# SMARTBALL_v2_2.net
KiCad netlist of a schematic drawn in EAGLE
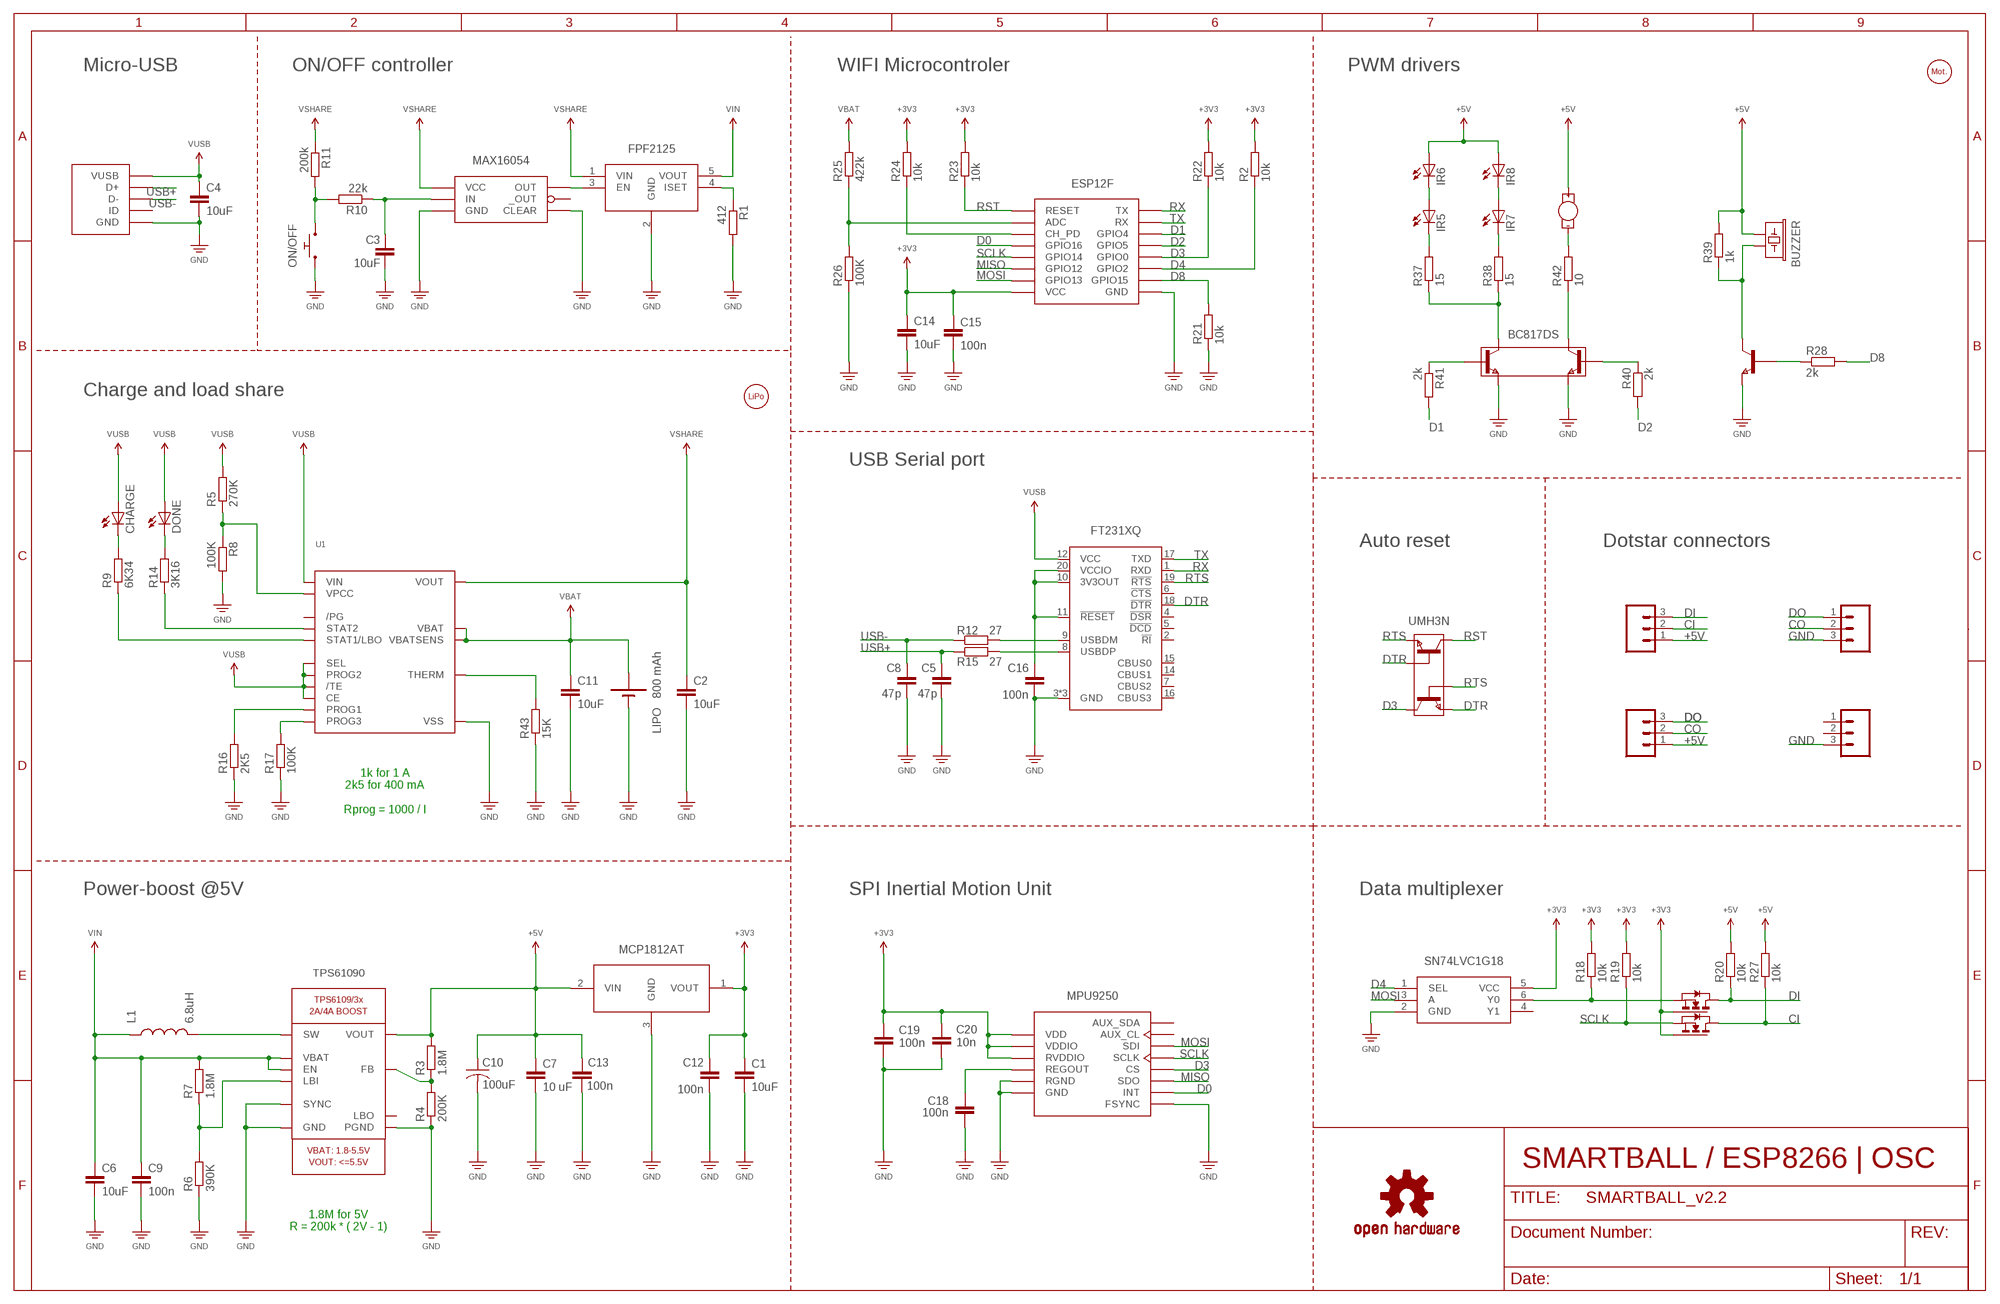
[diagram p0: schematic, sheet 1]

(export (version "E")
  (design (tool "Eeschema 10.0.6"))
  (components
    (comp (ref "BC817DS")
      (value "SOT_BC817DS")
      (footprint "eagle-import:SOT457R_PHILIPS")
      (libsource (lib "eagle-import") (part "SOT_BC817DS"))
    )
    (comp (ref "BUZZER")
      (value "BUZZER_PKMCS0909E4000-R1")
      (footprint "eagle-import:BUZZER_PKMCS0909E4000-R1")
      (libsource (lib "eagle-import") (part "BUZZER_PKMCS0909E4000-R1"))
    )
    (comp (ref "C1")
      (value "10uF")
      (footprint "eagle-import:C0603")
      (libsource (lib "eagle-import") (part "CAP_CERAMICC0603K"))
    )
    (comp (ref "C2")
      (value "10uF")
      (footprint "eagle-import:C0603")
      (libsource (lib "eagle-import") (part "CAP_CERAMICC0603K"))
    )
    (comp (ref "C3")
      (value "10uF")
      (footprint "eagle-import:C0603")
      (libsource (lib "eagle-import") (part "CAP_CERAMICC0603K"))
    )
    (comp (ref "C4")
      (value "10uF")
      (footprint "eagle-import:C0603")
      (libsource (lib "eagle-import") (part "CAP_CERAMICC0603K"))
    )
    (comp (ref "C5")
      (value "47p")
      (footprint "eagle-import:C0603")
      (libsource (lib "eagle-import") (part "CAP_CERAMICC0603K"))
    )
    (comp (ref "C6")
      (value "10uF")
      (footprint "eagle-import:C0603")
      (libsource (lib "eagle-import") (part "CAP_CERAMICC0603K"))
    )
    (comp (ref "C7")
      (value "10 uF")
      (footprint "eagle-import:C0603")
      (libsource (lib "eagle-import") (part "CAP_CERAMICC0603K"))
    )
    (comp (ref "C8")
      (value "47p")
      (footprint "eagle-import:C0603")
      (libsource (lib "eagle-import") (part "CAP_CERAMICC0603K"))
    )
    (comp (ref "C9")
      (value "100n")
      (footprint "eagle-import:C0603")
      (libsource (lib "eagle-import") (part "CAP_CERAMICC0603K"))
    )
    (comp (ref "C10")
      (value "100uF")
      (footprint "eagle-import:C1210")
      (libsource (lib "eagle-import") (part "CAP_TANTALUMC1210"))
    )
    (comp (ref "C11")
      (value "10uF")
      (footprint "eagle-import:C0603")
      (libsource (lib "eagle-import") (part "CAP_CERAMICC0603K"))
    )
    (comp (ref "C12")
      (value "100n")
      (footprint "eagle-import:C0603")
      (libsource (lib "eagle-import") (part "CAP_CERAMICC0603K"))
    )
    (comp (ref "C13")
      (value "100n")
      (footprint "eagle-import:C0603")
      (libsource (lib "eagle-import") (part "CAP_CERAMICC0603K"))
    )
    (comp (ref "C14")
      (value "10uF")
      (footprint "eagle-import:C0603")
      (libsource (lib "eagle-import") (part "CAP_CERAMICC0603K"))
    )
    (comp (ref "C15")
      (value "100n")
      (footprint "eagle-import:C0603")
      (libsource (lib "eagle-import") (part "CAP_CERAMICC0603K"))
    )
    (comp (ref "C16")
      (value "100n")
      (footprint "eagle-import:C0603")
      (libsource (lib "eagle-import") (part "CAP_CERAMICC0603K"))
    )
    (comp (ref "C18")
      (value "100n")
      (footprint "eagle-import:C0603")
      (libsource (lib "eagle-import") (part "CAP_CERAMICC0603K"))
    )
    (comp (ref "C19")
      (value "100n")
      (footprint "eagle-import:C0603")
      (libsource (lib "eagle-import") (part "CAP_CERAMICC0603K"))
    )
    (comp (ref "C20")
      (value "10n")
      (footprint "eagle-import:C0603")
      (libsource (lib "eagle-import") (part "CAP_CERAMICC0603K"))
    )
    (comp (ref "CHARGE")
      (value "LED_KINGBRIGHT_16X08")
      (footprint "eagle-import:LED_KINGBRIGHT_16X08")
      (libsource (lib "eagle-import") (part "LED_KINGBRIGHT_16X08"))
    )
    (comp (ref "DONE")
      (value "LED_KINGBRIGHT_16X08")
      (footprint "eagle-import:LED_KINGBRIGHT_16X08")
      (libsource (lib "eagle-import") (part "LED_KINGBRIGHT_16X08"))
    )
    (comp (ref "ESP12F")
      (value "µP_ESP12")
      (footprint "eagle-import:µP_ESP12")
      (libsource (lib "eagle-import") (part "µP_ESP12"))
    )
    (comp (ref "FT231XQ")
      (value "QFN_FT231X")
      (footprint "eagle-import:QFN20")
      (libsource (lib "eagle-import") (part "QFN_FT231X"))
    )
    (comp (ref "IR5")
      (value "LED_SFH4050")
      (footprint "eagle-import:LED_SFH4050")
      (libsource (lib "eagle-import") (part "LED_SFH4050"))
    )
    (comp (ref "IR6")
      (value "LED_SFH4050")
      (footprint "eagle-import:LED_SFH4050")
      (libsource (lib "eagle-import") (part "LED_SFH4050"))
    )
    (comp (ref "IR7")
      (value "LED_SFH4050")
      (footprint "eagle-import:LED_SFH4050")
      (libsource (lib "eagle-import") (part "LED_SFH4050"))
    )
    (comp (ref "IR8")
      (value "LED_SFH4050")
      (footprint "eagle-import:LED_SFH4050")
      (libsource (lib "eagle-import") (part "LED_SFH4050"))
    )
    (comp (ref "J1")
      (value "CONN_USB")
      (footprint "eagle-import:CONN_USB")
      (libsource (lib "eagle-import") (part "CONN_USB"))
    )
    (comp (ref "L1")
      (value "6.8uH")
      (footprint "eagle-import:IND_ASPIAIG-S4035")
      (libsource (lib "eagle-import") (part "IND_ASPIAIG-S4035"))
    )
    (comp (ref "LIPO")
      (value "CONN_BATTERY")
      (footprint "eagle-import:CONN_WIRES")
      (libsource (lib "eagle-import") (part "CONN_BATTERY"))
    )
    (comp (ref "LOGO1")
      (value "LOGO_OSHWL")
      (footprint "eagle-import:LOGO_OSHW")
      (libsource (lib "eagle-import") (part "LOGO_OSHWL"))
    )
    (comp (ref "MOTOR")
      (value "CONN_MOTOR")
      (footprint "eagle-import:CONN_WIRES")
      (libsource (lib "eagle-import") (part "CONN_MOTOR"))
    )
    (comp (ref "ON/OFF")
      (value "BUT_KMR6")
      (footprint "eagle-import:BUT_KMR6")
      (libsource (lib "eagle-import") (part "BUT_KMR6"))
    )
    (comp (ref "R1")
      (value "412")
      (footprint "eagle-import:R0402")
      (libsource (lib "eagle-import") (part "RES_EUR0402"))
    )
    (comp (ref "R2")
      (value "10k")
      (footprint "eagle-import:R0402")
      (libsource (lib "eagle-import") (part "RES_EUR0402"))
    )
    (comp (ref "R3")
      (value "1.8M")
      (footprint "eagle-import:R0402")
      (libsource (lib "eagle-import") (part "RES_EUR0402"))
    )
    (comp (ref "R4")
      (value "200K")
      (footprint "eagle-import:R0402")
      (libsource (lib "eagle-import") (part "RES_EUR0402"))
    )
    (comp (ref "R5")
      (value "270K")
      (footprint "eagle-import:R0402")
      (libsource (lib "eagle-import") (part "RES_EUR0402"))
    )
    (comp (ref "R6")
      (value "390K")
      (footprint "eagle-import:R0402")
      (libsource (lib "eagle-import") (part "RES_EUR0402"))
    )
    (comp (ref "R7")
      (value "1.8M")
      (footprint "eagle-import:R0402")
      (libsource (lib "eagle-import") (part "RES_EUR0402"))
    )
    (comp (ref "R8")
      (value "100K")
      (footprint "eagle-import:R0402")
      (libsource (lib "eagle-import") (part "RES_EUR0402"))
    )
    (comp (ref "R9")
      (value "6K34")
      (footprint "eagle-import:R0402")
      (libsource (lib "eagle-import") (part "RES_EUR0402"))
    )
    (comp (ref "R10")
      (value "22k")
      (footprint "eagle-import:R0402")
      (libsource (lib "eagle-import") (part "RES_EUR0402"))
    )
    (comp (ref "R11")
      (value "200k")
      (footprint "eagle-import:R0402")
      (libsource (lib "eagle-import") (part "RES_EUR0402"))
    )
    (comp (ref "R12")
      (value "27")
      (footprint "eagle-import:R0402")
      (libsource (lib "eagle-import") (part "RES_EUR0402"))
    )
    (comp (ref "R14")
      (value "3K16")
      (footprint "eagle-import:R0402")
      (libsource (lib "eagle-import") (part "RES_EUR0402"))
    )
    (comp (ref "R15")
      (value "27")
      (footprint "eagle-import:R0402")
      (libsource (lib "eagle-import") (part "RES_EUR0402"))
    )
    (comp (ref "R16")
      (value "2K5")
      (footprint "eagle-import:R0402")
      (libsource (lib "eagle-import") (part "RES_EUR0402"))
    )
    (comp (ref "R17")
      (value "100K")
      (footprint "eagle-import:R0402")
      (libsource (lib "eagle-import") (part "RES_EUR0402"))
    )
    (comp (ref "R18")
      (value "10k")
      (footprint "eagle-import:R0402")
      (libsource (lib "eagle-import") (part "RES_EUR0402"))
    )
    (comp (ref "R19")
      (value "10k")
      (footprint "eagle-import:R0402")
      (libsource (lib "eagle-import") (part "RES_EUR0402"))
    )
    (comp (ref "R20")
      (value "10k")
      (footprint "eagle-import:R0402")
      (libsource (lib "eagle-import") (part "RES_EUR0402"))
    )
    (comp (ref "R21")
      (value "10k")
      (footprint "eagle-import:R0402")
      (libsource (lib "eagle-import") (part "RES_EUR0402"))
    )
    (comp (ref "R22")
      (value "10k")
      (footprint "eagle-import:R0402")
      (libsource (lib "eagle-import") (part "RES_EUR0402"))
    )
    (comp (ref "R23")
      (value "10k")
      (footprint "eagle-import:R0402")
      (libsource (lib "eagle-import") (part "RES_EUR0402"))
    )
    (comp (ref "R24")
      (value "10k")
      (footprint "eagle-import:R0402")
      (libsource (lib "eagle-import") (part "RES_EUR0402"))
    )
    (comp (ref "R25")
      (value "422k")
      (footprint "eagle-import:R0402")
      (libsource (lib "eagle-import") (part "RES_EUR0402"))
    )
    (comp (ref "R26")
      (value "100K")
      (footprint "eagle-import:R0402")
      (libsource (lib "eagle-import") (part "RES_EUR0402"))
    )
    (comp (ref "R27")
      (value "10k")
      (footprint "eagle-import:R0402")
      (libsource (lib "eagle-import") (part "RES_EUR0402"))
    )
    (comp (ref "R28")
      (value "2k")
      (footprint "eagle-import:R0402")
      (libsource (lib "eagle-import") (part "RES_EUR0402"))
    )
    (comp (ref "R37")
      (value "15")
      (footprint "eagle-import:R0402")
      (libsource (lib "eagle-import") (part "RES_EUR0402"))
    )
    (comp (ref "R38")
      (value "15")
      (footprint "eagle-import:R0402")
      (libsource (lib "eagle-import") (part "RES_EUR0402"))
    )
    (comp (ref "R39")
      (value "1k")
      (footprint "eagle-import:R0402")
      (libsource (lib "eagle-import") (part "RES_EUR0402"))
    )
    (comp (ref "R40")
      (value "2k")
      (footprint "eagle-import:R0402")
      (libsource (lib "eagle-import") (part "RES_EUR0402"))
    )
    (comp (ref "R41")
      (value "2k")
      (footprint "eagle-import:R0402")
      (libsource (lib "eagle-import") (part "RES_EUR0402"))
    )
    (comp (ref "R42")
      (value "10")
      (footprint "eagle-import:R0402")
      (libsource (lib "eagle-import") (part "RES_EUR0402"))
    )
    (comp (ref "R43")
      (value "15K")
      (footprint "eagle-import:R0402")
      (libsource (lib "eagle-import") (part "RES_EUR0402"))
    )
    (comp (ref "TPS61090")
      (value "TPS61090RSAR")
      (footprint "eagle-import:QFN16")
      (libsource (lib "eagle-import") (part "QFN_TPS6103X"))
    )
    (comp (ref "U$2")
      (value "SOT_FPF2125")
      (footprint "eagle-import:SOT23-5")
      (libsource (lib "eagle-import") (part "SOT_FPF2125"))
    )
    (comp (ref "U$3")
      (value "SOT_MCP11812AT")
      (footprint "eagle-import:SOT23-3")
      (libsource (lib "eagle-import") (part "SOT_MCP11812AT"))
    )
    (comp (ref "U$5")
      (value "CONN_03_SMD")
      (footprint "eagle-import:CONN_03_SMD")
      (libsource (lib "eagle-import") (part "CONN_03_SMD"))
    )
    (comp (ref "U$6")
      (value "CONN_03_SMD")
      (footprint "eagle-import:CONN_03_SMD")
      (libsource (lib "eagle-import") (part "CONN_03_SMD"))
    )
    (comp (ref "U$12")
      (value "SOT_MAX16054")
      (footprint "eagle-import:TSOT23-6")
      (libsource (lib "eagle-import") (part "SOT_MAX16054"))
    )
    (comp (ref "U$14")
      (value "CONN_03_SMD")
      (footprint "eagle-import:CONN_03_SMD")
      (libsource (lib "eagle-import") (part "CONN_03_SMD"))
    )
    (comp (ref "U$15")
      (value "CONN_03_SMD")
      (footprint "eagle-import:CONN_03_SMD")
      (libsource (lib "eagle-import") (part "CONN_03_SMD"))
    )
    (comp (ref "U$19")
      (value "MOTOR_BODY")
      (footprint "eagle-import:MOTOR_BODY")
      (libsource (lib "eagle-import") (part "MOTOR_BODY"))
    )
    (comp (ref "U$20")
      (value "SOT_SN74LVC1G18")
      (footprint "eagle-import:SOT363")
      (libsource (lib "eagle-import") (part "SOT_SN74LVC1G18"))
    )
    (comp (ref "U$21")
      (value "QFN_MPU-9250QFN24G")
      (footprint "eagle-import:QFN24_3MM")
      (libsource (lib "eagle-import") (part "QFN_MPU-9250QFN24G"))
    )
    (comp (ref "U$22")
      (value "SOT_2N7002PS")
      (footprint "eagle-import:SOT363")
      (libsource (lib "eagle-import") (part "SOT_2N7002PS"))
    )
    (comp (ref "U$28")
      (value "SOT_SBC847AWT1G")
      (footprint "eagle-import:SOT323")
      (libsource (lib "eagle-import") (part "SOT_SBC847AWT1G"))
    )
    (comp (ref "U$29")
      (value "BATT_BODY")
      (footprint "eagle-import:BATT_BODY")
      (libsource (lib "eagle-import") (part "BATT_BODY"))
    )
    (comp (ref "U1")
      (value "QFN_MCP73871")
      (footprint "eagle-import:QFN20")
      (libsource (lib "eagle-import") (part "QFN_MCP73871"))
    )
    (comp (ref "UMH3N")
      (value "SOT_UMH3N")
      (footprint "eagle-import:SOT363")
      (libsource (lib "eagle-import") (part "SOT_UMH3N"))
    )
  )
  (nets
    (net (code "1") (name "+3V3") (class "Default")
      (node (ref "C1") (pin "1") (pinfunction "1_1") (pintype "passive"))
      (node (ref "C12") (pin "1") (pinfunction "1_1") (pintype "passive"))
      (node (ref "C14") (pin "1") (pinfunction "1_1") (pintype "passive"))
      (node (ref "C15") (pin "1") (pinfunction "1_1") (pintype "passive"))
      (node (ref "C19") (pin "1") (pinfunction "1_1") (pintype "passive"))
      (node (ref "C20") (pin "2") (pinfunction "2_2") (pintype "passive"))
      (node (ref "ESP12F") (pin "VCC") (pinfunction "VCC_VCC") (pintype "bidirectional"))
      (node (ref "R18") (pin "2") (pinfunction "2_2") (pintype "passive"))
      (node (ref "R19") (pin "2") (pinfunction "2_2") (pintype "passive"))
      (node (ref "R2") (pin "2") (pinfunction "2_2") (pintype "passive"))
      (node (ref "R22") (pin "2") (pinfunction "2_2") (pintype "passive"))
      (node (ref "R23") (pin "2") (pinfunction "2_2") (pintype "passive"))
      (node (ref "R24") (pin "2") (pinfunction "2_2") (pintype "passive"))
      (node (ref "U$20") (pin "5") (pinfunction "VCC_5") (pintype "bidirectional"))
      (node (ref "U$21") (pin "1") (pinfunction "RVDDIO_1") (pintype "bidirectional"))
      (node (ref "U$21") (pin "13") (pinfunction "VDD_13") (pintype "bidirectional"))
      (node (ref "U$21") (pin "8") (pinfunction "VDDIO_8") (pintype "bidirectional"))
      (node (ref "U$22") (pin "2") (pinfunction "G1_2") (pintype "passive"))
      (node (ref "U$22") (pin "5") (pinfunction "G2_5") (pintype "passive"))
      (node (ref "U$3") (pin "1") (pinfunction "VOUT_1") (pintype "bidirectional"))
    )
    (net (code "2") (name "+5V") (class "Default")
      (node (ref "BUZZER") (pin "1") (pinfunction "1_1") (pintype "passive"))
      (node (ref "C10") (pin "1") (pinfunction "1_1") (pintype "passive"))
      (node (ref "C13") (pin "1") (pinfunction "1_1") (pintype "passive"))
      (node (ref "C7") (pin "1") (pinfunction "1_1") (pintype "passive"))
      (node (ref "IR6") (pin "1") (pinfunction "A_1") (pintype "passive"))
      (node (ref "IR8") (pin "1") (pinfunction "A_1") (pintype "passive"))
      (node (ref "MOTOR") (pin "VCC") (pinfunction "+_VCC") (pintype "bidirectional"))
      (node (ref "R20") (pin "2") (pinfunction "2_2") (pintype "passive"))
      (node (ref "R27") (pin "2") (pinfunction "2_2") (pintype "passive"))
      (node (ref "R3") (pin "2") (pinfunction "2_2") (pintype "passive"))
      (node (ref "R39") (pin "2") (pinfunction "2_2") (pintype "passive"))
      (node (ref "TPS61090") (pin "1") (pinfunction "VOUT_1") (pintype "power_in"))
      (node (ref "TPS61090") (pin "15") (pinfunction "VOUT_15") (pintype "power_in"))
      (node (ref "TPS61090") (pin "16") (pinfunction "VOUT_16") (pintype "power_in"))
      (node (ref "U$15") (pin "1") (pinfunction "1_1") (pintype "passive"))
      (node (ref "U$3") (pin "2") (pinfunction "VIN_2") (pintype "bidirectional"))
      (node (ref "U$5") (pin "1") (pinfunction "1_1") (pintype "passive"))
    )
    (net (code "3") (name "/CI") (class "Default")
      (node (ref "R27") (pin "1") (pinfunction "1_1") (pintype "passive"))
      (node (ref "U$22") (pin "3") (pinfunction "D2_3") (pintype "passive"))
      (node (ref "U$5") (pin "2") (pinfunction "2_2") (pintype "passive"))
    )
    (net (code "4") (name "/CO") (class "Default")
      (node (ref "U$15") (pin "2") (pinfunction "2_2") (pintype "passive"))
      (node (ref "U$6") (pin "2") (pinfunction "2_2") (pintype "passive"))
    )
    (net (code "5") (name "/D0") (class "Default")
      (node (ref "ESP12F") (pin "GPIO16") (pinfunction "GPIO16_GPIO16") (pintype "bidirectional"))
      (node (ref "U$21") (pin "12") (pinfunction "INT_12") (pintype "bidirectional"))
    )
    (net (code "6") (name "/D1") (class "Default")
      (node (ref "ESP12F") (pin "GPIO4") (pinfunction "GPIO4_GPIO4") (pintype "bidirectional"))
      (node (ref "R41") (pin "2") (pinfunction "2_2") (pintype "passive"))
    )
    (net (code "7") (name "/D2") (class "Default")
      (node (ref "ESP12F") (pin "GPIO5") (pinfunction "GPIO5_GPIO5") (pintype "bidirectional"))
      (node (ref "R40") (pin "2") (pinfunction "2_2") (pintype "passive"))
    )
    (net (code "8") (name "/D3") (class "Default")
      (node (ref "ESP12F") (pin "GPIO0") (pinfunction "GPIO0_GPIO0") (pintype "bidirectional"))
      (node (ref "R22") (pin "1") (pinfunction "1_1") (pintype "passive"))
      (node (ref "U$21") (pin "22") (pinfunction "CS_22") (pintype "bidirectional"))
      (node (ref "UMH3N") (pin "3") (pinfunction "C2_3") (pintype "passive"))
    )
    (net (code "9") (name "/D4") (class "Default")
      (node (ref "ESP12F") (pin "GPIO2") (pinfunction "GPIO2_GPIO2") (pintype "bidirectional"))
      (node (ref "R2") (pin "1") (pinfunction "1_1") (pintype "passive"))
      (node (ref "U$20") (pin "1") (pinfunction "SEL_1") (pintype "bidirectional"))
    )
    (net (code "10") (name "/D8") (class "Default")
      (node (ref "ESP12F") (pin "GPIO15") (pinfunction "GPIO15_GPIO15") (pintype "bidirectional"))
      (node (ref "R21") (pin "2") (pinfunction "2_2") (pintype "passive"))
      (node (ref "R28") (pin "2") (pinfunction "2_2") (pintype "passive"))
    )
    (net (code "11") (name "/DI") (class "Default")
      (node (ref "R20") (pin "1") (pinfunction "1_1") (pintype "passive"))
      (node (ref "U$22") (pin "6") (pinfunction "D1_6") (pintype "passive"))
      (node (ref "U$5") (pin "3") (pinfunction "3_3") (pintype "passive"))
    )
    (net (code "12") (name "/DO") (class "Default")
      (node (ref "U$15") (pin "3") (pinfunction "3_3") (pintype "passive"))
      (node (ref "U$6") (pin "1") (pinfunction "1_1") (pintype "passive"))
    )
    (net (code "13") (name "/DTR") (class "Default")
      (node (ref "FT231XQ") (pin "18") (pinfunction "~{DTR}_18") (pintype "bidirectional"))
      (node (ref "UMH3N") (pin "2") (pinfunction "B1_2") (pintype "passive"))
      (node (ref "UMH3N") (pin "4") (pinfunction "E2_4") (pintype "passive"))
    )
    (net (code "14") (name "/MISO") (class "Default")
      (node (ref "ESP12F") (pin "GPIO12") (pinfunction "GPIO12_GPIO12") (pintype "bidirectional"))
      (node (ref "U$21") (pin "9") (pinfunction "SDO_9") (pintype "bidirectional"))
    )
    (net (code "15") (name "/MOSI") (class "Default")
      (node (ref "ESP12F") (pin "GPIO13") (pinfunction "GPIO13_GPIO13") (pintype "bidirectional"))
      (node (ref "U$20") (pin "3") (pinfunction "A_3") (pintype "bidirectional"))
      (node (ref "U$21") (pin "24") (pinfunction "SDI_24") (pintype "bidirectional"))
    )
    (net (code "16") (name "/RST") (class "Default")
      (node (ref "ESP12F") (pin "RESET") (pinfunction "RESET_RESET") (pintype "bidirectional"))
      (node (ref "R23") (pin "1") (pinfunction "1_1") (pintype "passive"))
      (node (ref "UMH3N") (pin "6") (pinfunction "C1_6") (pintype "passive"))
    )
    (net (code "17") (name "/RTS") (class "Default")
      (node (ref "FT231XQ") (pin "19") (pinfunction "~{RTS}_19") (pintype "bidirectional"))
      (node (ref "UMH3N") (pin "1") (pinfunction "E1_1") (pintype "passive"))
      (node (ref "UMH3N") (pin "5") (pinfunction "B2_5") (pintype "passive"))
    )
    (net (code "18") (name "/RX") (class "Default")
      (node (ref "ESP12F") (pin "TX") (pinfunction "TX_TX") (pintype "bidirectional"))
      (node (ref "FT231XQ") (pin "1") (pinfunction "RXD_1") (pintype "bidirectional"))
    )
    (net (code "19") (name "/SCLK") (class "Default")
      (node (ref "ESP12F") (pin "GPIO14") (pinfunction "GPIO14_GPIO14") (pintype "bidirectional"))
      (node (ref "R19") (pin "1") (pinfunction "1_1") (pintype "passive"))
      (node (ref "U$21") (pin "23") (pinfunction "SCLK_23") (pintype "bidirectional"))
      (node (ref "U$22") (pin "4") (pinfunction "S2_4") (pintype "passive"))
    )
    (net (code "20") (name "/TX") (class "Default")
      (node (ref "ESP12F") (pin "RX") (pinfunction "RX_RX") (pintype "bidirectional"))
      (node (ref "FT231XQ") (pin "17") (pinfunction "TXD_17") (pintype "bidirectional"))
    )
    (net (code "21") (name "/USB+") (class "Default")
      (node (ref "C5") (pin "1") (pinfunction "1_1") (pintype "passive"))
      (node (ref "J1") (pin "D+") (pinfunction "D+_D+") (pintype "bidirectional"))
      (node (ref "R15") (pin "1") (pinfunction "1_1") (pintype "passive"))
    )
    (net (code "22") (name "/USB-") (class "Default")
      (node (ref "C8") (pin "1") (pinfunction "1_1") (pintype "passive"))
      (node (ref "J1") (pin "D-") (pinfunction "D-_D-") (pintype "bidirectional"))
      (node (ref "R12") (pin "1") (pinfunction "1_1") (pintype "passive"))
    )
    (net (code "23") (name "GND") (class "Default")
      (node (ref "BC817DS") (pin "1") (pinfunction "E1_1") (pintype "passive"))
      (node (ref "BC817DS") (pin "4") (pinfunction "E2_4") (pintype "passive"))
      (node (ref "C1") (pin "2") (pinfunction "2_2") (pintype "passive"))
      (node (ref "C10") (pin "2") (pinfunction "2_2") (pintype "passive"))
      (node (ref "C11") (pin "2") (pinfunction "2_2") (pintype "passive"))
      (node (ref "C12") (pin "2") (pinfunction "2_2") (pintype "passive"))
      (node (ref "C13") (pin "2") (pinfunction "2_2") (pintype "passive"))
      (node (ref "C14") (pin "2") (pinfunction "2_2") (pintype "passive"))
      (node (ref "C15") (pin "2") (pinfunction "2_2") (pintype "passive"))
      (node (ref "C16") (pin "2") (pinfunction "2_2") (pintype "passive"))
      (node (ref "C18") (pin "2") (pinfunction "2_2") (pintype "passive"))
      (node (ref "C19") (pin "2") (pinfunction "2_2") (pintype "passive"))
      (node (ref "C2") (pin "2") (pinfunction "2_2") (pintype "passive"))
      (node (ref "C20") (pin "1") (pinfunction "1_1") (pintype "passive"))
      (node (ref "C3") (pin "2") (pinfunction "2_2") (pintype "passive"))
      (node (ref "C4") (pin "2") (pinfunction "2_2") (pintype "passive"))
      (node (ref "C5") (pin "2") (pinfunction "2_2") (pintype "passive"))
      (node (ref "C6") (pin "2") (pinfunction "2_2") (pintype "passive"))
      (node (ref "C7") (pin "2") (pinfunction "2_2") (pintype "passive"))
      (node (ref "C8") (pin "2") (pinfunction "2_2") (pintype "passive"))
      (node (ref "C9") (pin "2") (pinfunction "2_2") (pintype "passive"))
      (node (ref "ESP12F") (pin "GND") (pinfunction "GND_GND") (pintype "bidirectional"))
      (node (ref "FT231XQ") (pin "13") (pinfunction "GND_13") (pintype "bidirectional"))
      (node (ref "FT231XQ") (pin "3") (pinfunction "GND_3") (pintype "bidirectional"))
      (node (ref "FT231XQ") (pin "EXP") (pinfunction "GND_EXP") (pintype "bidirectional"))
      (node (ref "J1") (pin "GND") (pinfunction "GND_GND") (pintype "bidirectional"))
      (node (ref "J1") (pin "P$1") (pinfunction "GND_P$1") (pintype "bidirectional"))
      (node (ref "J1") (pin "P$11") (pinfunction "GND_P$11") (pintype "bidirectional"))
      (node (ref "J1") (pin "SHELL1") (pinfunction "GND_SHELL1") (pintype "bidirectional"))
      (node (ref "J1") (pin "SHELL2") (pinfunction "GND_SHELL2") (pintype "bidirectional"))
      (node (ref "J1") (pin "SHELL5") (pinfunction "GND_SHELL5") (pintype "bidirectional"))
      (node (ref "J1") (pin "SHELL6") (pinfunction "GND_SHELL6") (pintype "bidirectional"))
      (node (ref "LIPO") (pin "GND") (pinfunction "GND_GND") (pintype "power_in"))
      (node (ref "ON/OFF") (pin "1") (pinfunction "1_1") (pintype "passive"))
      (node (ref "ON/OFF") (pin "4") (pinfunction "1_4") (pintype "passive"))
      (node (ref "R1") (pin "2") (pinfunction "2_2") (pintype "passive"))
      (node (ref "R16") (pin "1") (pinfunction "1_1") (pintype "passive"))
      (node (ref "R17") (pin "1") (pinfunction "1_1") (pintype "passive"))
      (node (ref "R21") (pin "1") (pinfunction "1_1") (pintype "passive"))
      (node (ref "R26") (pin "1") (pinfunction "1_1") (pintype "passive"))
      (node (ref "R4") (pin "1") (pinfunction "1_1") (pintype "passive"))
      (node (ref "R43") (pin "1") (pinfunction "1_1") (pintype "passive"))
      (node (ref "R6") (pin "1") (pinfunction "1_1") (pintype "passive"))
      (node (ref "R8") (pin "2") (pinfunction "2_2") (pintype "passive"))
      (node (ref "TPS61090") (pin "10") (pinfunction "SYNC_10") (pintype "input"))
      (node (ref "TPS61090") (pin "13") (pinfunction "GND_13") (pintype "power_in"))
      (node (ref "TPS61090") (pin "5") (pinfunction "PGND_5") (pintype "power_in"))
      (node (ref "TPS61090") (pin "6") (pinfunction "PGND_6") (pintype "power_in"))
      (node (ref "TPS61090") (pin "7") (pinfunction "PGND_7") (pintype "power_in"))
      (node (ref "TPS61090") (pin "PAD") (pinfunction "PGND_PAD") (pintype "power_in"))
      (node (ref "U$12") (pin "2") (pinfunction "GND_2") (pintype "bidirectional"))
      (node (ref "U$12") (pin "3") (pinfunction "CLEAR_3") (pintype "bidirectional"))
      (node (ref "U$14") (pin "3") (pinfunction "3_3") (pintype "passive"))
      (node (ref "U$2") (pin "2") (pinfunction "GND_2") (pintype "bidirectional"))
      (node (ref "U$20") (pin "2") (pinfunction "GND_2") (pintype "bidirectional"))
      (node (ref "U$21") (pin "11") (pinfunction "FSYNC_11") (pintype "bidirectional"))
      (node (ref "U$21") (pin "18") (pinfunction "GND_18") (pintype "bidirectional"))
      (node (ref "U$21") (pin "20") (pinfunction "RGND_20") (pintype "bidirectional"))
      (node (ref "U$28") (pin "2") (pinfunction "E_2") (pintype "passive"))
      (node (ref "U$3") (pin "3") (pinfunction "GND_3") (pintype "bidirectional"))
      (node (ref "U$6") (pin "3") (pinfunction "3_3") (pintype "passive"))
      (node (ref "U1") (pin "10") (pinfunction "VSS_10") (pintype "bidirectional"))
      (node (ref "U1") (pin "11") (pinfunction "VSS_11") (pintype "bidirectional"))
      (node (ref "U1") (pin "EXP") (pinfunction "VSS_EXP") (pintype "bidirectional"))
    )
    (net (code "24") (name "Net-(BC817DS-B1)") (class "Default")
      (node (ref "BC817DS") (pin "2") (pinfunction "B1_2") (pintype "passive"))
      (node (ref "R40") (pin "1") (pinfunction "1_1") (pintype "passive"))
    )
    (net (code "25") (name "Net-(BC817DS-B2)") (class "Default")
      (node (ref "BC817DS") (pin "5") (pinfunction "B2_5") (pintype "passive"))
      (node (ref "R41") (pin "1") (pinfunction "1_1") (pintype "passive"))
    )
    (net (code "26") (name "Net-(BC817DS-C1)") (class "Default")
      (node (ref "BC817DS") (pin "6") (pinfunction "C1_6") (pintype "passive"))
      (node (ref "R42") (pin "1") (pinfunction "1_1") (pintype "passive"))
    )
    (net (code "27") (name "Net-(BC817DS-C2)") (class "Default")
      (node (ref "BC817DS") (pin "3") (pinfunction "C2_3") (pintype "passive"))
      (node (ref "R37") (pin "1") (pinfunction "1_1") (pintype "passive"))
      (node (ref "R38") (pin "1") (pinfunction "1_1") (pintype "passive"))
    )
    (net (code "28") (name "Net-(CHARGE-C)") (class "Default")
      (node (ref "CHARGE") (pin "2") (pinfunction "C_2") (pintype "passive"))
      (node (ref "R9") (pin "2") (pinfunction "2_2") (pintype "passive"))
    )
    (net (code "29") (name "Net-(DONE-C)") (class "Default")
      (node (ref "DONE") (pin "2") (pinfunction "C_2") (pintype "passive"))
      (node (ref "R14") (pin "2") (pinfunction "2_2") (pintype "passive"))
    )
    (net (code "30") (name "Net-(ESP12F-PadADC)") (class "Default")
      (node (ref "ESP12F") (pin "ADC") (pinfunction "ADC_ADC") (pintype "bidirectional"))
      (node (ref "R25") (pin "1") (pinfunction "1_1") (pintype "passive"))
      (node (ref "R26") (pin "2") (pinfunction "2_2") (pintype "passive"))
    )
    (net (code "31") (name "Net-(ESP12F-PadCH_PD)") (class "Default")
      (node (ref "ESP12F") (pin "CH_PD") (pinfunction "CH_PD_CH_PD") (pintype "bidirectional"))
      (node (ref "R24") (pin "1") (pinfunction "1_1") (pintype "passive"))
    )
    (net (code "32") (name "Net-(FT231XQ-3V3OUT)") (class "Default")
      (node (ref "C16") (pin "1") (pinfunction "1_1") (pintype "passive"))
      (node (ref "FT231XQ") (pin "10") (pinfunction "3V3OUT_10") (pintype "bidirectional"))
      (node (ref "FT231XQ") (pin "11") (pinfunction "~{RESET}_11") (pintype "bidirectional"))
      (node (ref "FT231XQ") (pin "20") (pinfunction "VCCIO_20") (pintype "bidirectional"))
    )
    (net (code "33") (name "Net-(FT231XQ-USBDM)") (class "Default")
      (node (ref "FT231XQ") (pin "9") (pinfunction "USBDM_9") (pintype "bidirectional"))
      (node (ref "R12") (pin "2") (pinfunction "2_2") (pintype "passive"))
    )
    (net (code "34") (name "Net-(FT231XQ-USBDP)") (class "Default")
      (node (ref "FT231XQ") (pin "8") (pinfunction "USBDP_8") (pintype "bidirectional"))
      (node (ref "R15") (pin "2") (pinfunction "2_2") (pintype "passive"))
    )
    (net (code "35") (name "Net-(IR5-A)") (class "Default")
      (node (ref "IR5") (pin "1") (pinfunction "A_1") (pintype "passive"))
      (node (ref "IR6") (pin "2") (pinfunction "C_2") (pintype "passive"))
    )
    (net (code "36") (name "Net-(IR5-C)") (class "Default")
      (node (ref "IR5") (pin "2") (pinfunction "C_2") (pintype "passive"))
      (node (ref "R37") (pin "2") (pinfunction "2_2") (pintype "passive"))
    )
    (net (code "37") (name "Net-(IR7-A)") (class "Default")
      (node (ref "IR7") (pin "1") (pinfunction "A_1") (pintype "passive"))
      (node (ref "IR8") (pin "2") (pinfunction "C_2") (pintype "passive"))
    )
    (net (code "38") (name "Net-(IR7-C)") (class "Default")
      (node (ref "IR7") (pin "2") (pinfunction "C_2") (pintype "passive"))
      (node (ref "R38") (pin "2") (pinfunction "2_2") (pintype "passive"))
    )
    (net (code "39") (name "Net-(L1-Pad2)") (class "Default")
      (node (ref "L1") (pin "2") (pinfunction "2_2") (pintype "passive"))
      (node (ref "TPS61090") (pin "3") (pinfunction "SW_3") (pintype "input"))
      (node (ref "TPS61090") (pin "4") (pinfunction "SW_4") (pintype "input"))
    )
    (net (code "40") (name "Net-(MOTOR--)") (class "Default")
      (node (ref "MOTOR") (pin "GND") (pinfunction "-_GND") (pintype "bidirectional"))
      (node (ref "R42") (pin "2") (pinfunction "2_2") (pintype "passive"))
    )
    (net (code "41") (name "Net-(ON/OFF-2-Pad3)") (class "Default")
      (node (ref "ON/OFF") (pin "2") (pinfunction "2_2") (pintype "passive"))
      (node (ref "ON/OFF") (pin "3") (pinfunction "2_3") (pintype "passive"))
      (node (ref "R10") (pin "2") (pinfunction "2_2") (pintype "passive"))
      (node (ref "R11") (pin "2") (pinfunction "2_2") (pintype "passive"))
    )
    (net (code "42") (name "Net-(TPS61090-FB)") (class "Default")
      (node (ref "R3") (pin "1") (pinfunction "1_1") (pintype "passive"))
      (node (ref "R4") (pin "2") (pinfunction "2_2") (pintype "passive"))
      (node (ref "TPS61090") (pin "14") (pinfunction "FB_14") (pintype "input"))
    )
    (net (code "43") (name "Net-(TPS61090-LBI)") (class "Default")
      (node (ref "R6") (pin "2") (pinfunction "2_2") (pintype "passive"))
      (node (ref "R7") (pin "1") (pinfunction "1_1") (pintype "passive"))
      (node (ref "TPS61090") (pin "9") (pinfunction "LBI_9") (pintype "input"))
    )
    (net (code "44") (name "Net-(U$2-ISET)") (class "Default")
      (node (ref "R1") (pin "1") (pinfunction "1_1") (pintype "passive"))
      (node (ref "U$2") (pin "4") (pinfunction "ISET_4") (pintype "bidirectional"))
    )
    (net (code "45") (name "Net-(U$12-IN)") (class "Default")
      (node (ref "C3") (pin "1") (pinfunction "1_1") (pintype "passive"))
      (node (ref "R10") (pin "1") (pinfunction "1_1") (pintype "passive"))
      (node (ref "U$12") (pin "1") (pinfunction "IN_1") (pintype "bidirectional"))
    )
    (net (code "46") (name "Net-(U$12-OUT)") (class "Default")
      (node (ref "U$12") (pin "5") (pinfunction "OUT_5") (pintype "bidirectional"))
      (node (ref "U$2") (pin "3") (pinfunction "EN_3") (pintype "bidirectional"))
    )
    (net (code "47") (name "Net-(U$20-Y0)") (class "Default")
      (node (ref "R18") (pin "1") (pinfunction "1_1") (pintype "passive"))
      (node (ref "U$20") (pin "6") (pinfunction "Y0_6") (pintype "bidirectional"))
      (node (ref "U$22") (pin "1") (pinfunction "S1_1") (pintype "passive"))
    )
    (net (code "48") (name "Net-(U$21-REGOUT)") (class "Default")
      (node (ref "C18") (pin "1") (pinfunction "1_1") (pintype "passive"))
      (node (ref "U$21") (pin "10") (pinfunction "REGOUT_10") (pintype "bidirectional"))
    )
    (net (code "49") (name "Net-(U$28-B)") (class "Default")
      (node (ref "R28") (pin "1") (pinfunction "1_1") (pintype "passive"))
      (node (ref "U$28") (pin "1") (pinfunction "B_1") (pintype "passive"))
    )
    (net (code "50") (name "Net-(U$28-C)") (class "Default")
      (node (ref "BUZZER") (pin "2") (pinfunction "2_2") (pintype "passive"))
      (node (ref "R39") (pin "1") (pinfunction "1_1") (pintype "passive"))
      (node (ref "U$28") (pin "3") (pinfunction "C_3") (pintype "passive"))
    )
    (net (code "51") (name "Net-(U1-PROG1)") (class "Default")
      (node (ref "R16") (pin "2") (pinfunction "2_2") (pintype "passive"))
      (node (ref "U1") (pin "13") (pinfunction "PROG1_13") (pintype "bidirectional"))
    )
    (net (code "52") (name "Net-(U1-PROG3)") (class "Default")
      (node (ref "R17") (pin "2") (pinfunction "2_2") (pintype "passive"))
      (node (ref "U1") (pin "12") (pinfunction "PROG3_12") (pintype "bidirectional"))
    )
    (net (code "53") (name "Net-(U1-STAT1{slash}LBO)") (class "Default")
      (node (ref "R9") (pin "1") (pinfunction "1_1") (pintype "passive"))
      (node (ref "U1") (pin "8") (pinfunction "STAT1/LBO_8") (pintype "bidirectional"))
    )
    (net (code "54") (name "Net-(U1-STAT2)") (class "Default")
      (node (ref "R14") (pin "1") (pinfunction "1_1") (pintype "passive"))
      (node (ref "U1") (pin "7") (pinfunction "STAT2_7") (pintype "bidirectional"))
    )
    (net (code "55") (name "Net-(U1-THERM)") (class "Default")
      (node (ref "R43") (pin "2") (pinfunction "2_2") (pintype "passive"))
      (node (ref "U1") (pin "5") (pinfunction "THERM_5") (pintype "bidirectional"))
    )
    (net (code "56") (name "Net-(U1-VPCC)") (class "Default")
      (node (ref "R5") (pin "1") (pinfunction "1_1") (pintype "passive"))
      (node (ref "R8") (pin "1") (pinfunction "1_1") (pintype "passive"))
      (node (ref "U1") (pin "2") (pinfunction "VPCC_2") (pintype "bidirectional"))
    )
    (net (code "57") (name "VBAT") (class "Default")
      (node (ref "C11") (pin "1") (pinfunction "1_1") (pintype "passive"))
      (node (ref "LIPO") (pin "VCC") (pinfunction "VBAT_VCC") (pintype "power_in"))
      (node (ref "R25") (pin "2") (pinfunction "2_2") (pintype "passive"))
      (node (ref "U1") (pin "14") (pinfunction "VBAT_14") (pintype "bidirectional"))
      (node (ref "U1") (pin "15") (pinfunction "VBAT_15") (pintype "bidirectional"))
      (node (ref "U1") (pin "16") (pinfunction "VBATSENS_16") (pintype "bidirectional"))
    )
    (net (code "58") (name "VIN") (class "Default")
      (node (ref "C6") (pin "1") (pinfunction "1_1") (pintype "passive"))
      (node (ref "C9") (pin "1") (pinfunction "1_1") (pintype "passive"))
      (node (ref "L1") (pin "1") (pinfunction "1_1") (pintype "passive"))
      (node (ref "R7") (pin "2") (pinfunction "2_2") (pintype "passive"))
      (node (ref "TPS61090") (pin "11") (pinfunction "EN_11") (pintype "input"))
      (node (ref "TPS61090") (pin "8") (pinfunction "VBAT_8") (pintype "input"))
      (node (ref "U$2") (pin "5") (pinfunction "VOUT_5") (pintype "bidirectional"))
    )
    (net (code "59") (name "VSHARE") (class "Default")
      (node (ref "C2") (pin "1") (pinfunction "1_1") (pintype "passive"))
      (node (ref "R11") (pin "1") (pinfunction "1_1") (pintype "passive"))
      (node (ref "U$12") (pin "6") (pinfunction "VCC_6") (pintype "bidirectional"))
      (node (ref "U$2") (pin "1") (pinfunction "VIN_1") (pintype "bidirectional"))
      (node (ref "U1") (pin "1") (pinfunction "VOUT_1") (pintype "bidirectional"))
      (node (ref "U1") (pin "20") (pinfunction "VOUT_20") (pintype "bidirectional"))
    )
    (net (code "60") (name "VUSB") (class "Default")
      (node (ref "C4") (pin "1") (pinfunction "1_1") (pintype "passive"))
      (node (ref "CHARGE") (pin "1") (pinfunction "A_1") (pintype "passive"))
      (node (ref "DONE") (pin "1") (pinfunction "A_1") (pintype "passive"))
      (node (ref "FT231XQ") (pin "12") (pinfunction "VCC_12") (pintype "bidirectional"))
      (node (ref "J1") (pin "VUSB") (pinfunction "VUSB_VUSB") (pintype "bidirectional"))
      (node (ref "R5") (pin "2") (pinfunction "2_2") (pintype "passive"))
      (node (ref "U1") (pin "17") (pinfunction "CE_17") (pintype "bidirectional"))
      (node (ref "U1") (pin "18") (pinfunction "VIN_18") (pintype "bidirectional"))
      (node (ref "U1") (pin "19") (pinfunction "VIN_19") (pintype "bidirectional"))
      (node (ref "U1") (pin "3") (pinfunction "SEL_3") (pintype "bidirectional"))
      (node (ref "U1") (pin "4") (pinfunction "PROG2_4") (pintype "bidirectional"))
      (node (ref "U1") (pin "9") (pinfunction "/TE_9") (pintype "bidirectional"))
    )
    (net (code "61") (name "unconnected-(FT231XQ-CBUS0-Pad15)") (class "Default")
      (node (ref "FT231XQ") (pin "15") (pinfunction "CBUS0_15") (pintype "bidirectional"))
    )
    (net (code "62") (name "unconnected-(FT231XQ-CBUS1-Pad14)") (class "Default")
      (node (ref "FT231XQ") (pin "14") (pinfunction "CBUS1_14") (pintype "bidirectional"))
    )
    (net (code "63") (name "unconnected-(FT231XQ-CBUS2-Pad7)") (class "Default")
      (node (ref "FT231XQ") (pin "7") (pinfunction "CBUS2_7") (pintype "bidirectional"))
    )
    (net (code "64") (name "unconnected-(FT231XQ-CBUS3-Pad16)") (class "Default")
      (node (ref "FT231XQ") (pin "16") (pinfunction "CBUS3_16") (pintype "bidirectional"))
    )
    (net (code "65") (name "unconnected-(FT231XQ-~{CTS}-Pad6)") (class "Default")
      (node (ref "FT231XQ") (pin "6") (pinfunction "~{CTS}_6") (pintype "bidirectional"))
    )
    (net (code "66") (name "unconnected-(FT231XQ-~{DCD}-Pad5)") (class "Default")
      (node (ref "FT231XQ") (pin "5") (pinfunction "~{DCD}_5") (pintype "bidirectional"))
    )
    (net (code "67") (name "unconnected-(FT231XQ-~{DSR}-Pad4)") (class "Default")
      (node (ref "FT231XQ") (pin "4") (pinfunction "~{DSR}_4") (pintype "bidirectional"))
    )
    (net (code "68") (name "unconnected-(FT231XQ-~{RI}-Pad2)") (class "Default")
      (node (ref "FT231XQ") (pin "2") (pinfunction "~{RI}_2") (pintype "bidirectional"))
    )
    (net (code "69") (name "unconnected-(J1-PadID)") (class "Default")
      (node (ref "J1") (pin "ID") (pinfunction "ID_ID") (pintype "bidirectional"))
    )
    (net (code "70") (name "unconnected-(TPS61090-LBO-Pad12)") (class "Default")
      (node (ref "TPS61090") (pin "12") (pinfunction "LBO_12") (pintype "output"))
    )
    (net (code "71") (name "unconnected-(U$12-_OUT-Pad4)") (class "Default")
      (node (ref "U$12") (pin "4") (pinfunction "_OUT_4") (pintype "bidirectional"))
    )
    (net (code "72") (name "unconnected-(U$14-Pad1)") (class "Default")
      (node (ref "U$14") (pin "1") (pinfunction "1_1") (pintype "passive"))
    )
    (net (code "73") (name "unconnected-(U$14-Pad2)") (class "Default")
      (node (ref "U$14") (pin "2") (pinfunction "2_2") (pintype "passive"))
    )
    (net (code "74") (name "unconnected-(U$20-Y1-Pad4)") (class "Default")
      (node (ref "U$20") (pin "4") (pinfunction "Y1_4") (pintype "bidirectional"))
    )
    (net (code "75") (name "unconnected-(U$21-AUX_CL-Pad7)") (class "Default")
      (node (ref "U$21") (pin "7") (pinfunction "AUX_CL_7") (pintype "bidirectional"))
    )
    (net (code "76") (name "unconnected-(U$21-AUX_SDA-Pad21)") (class "Default")
      (node (ref "U$21") (pin "21") (pinfunction "AUX_SDA_21") (pintype "bidirectional"))
    )
    (net (code "77") (name "unconnected-(U1-{slash}PG-Pad6)") (class "Default")
      (node (ref "U1") (pin "6") (pinfunction "/PG_6") (pintype "bidirectional"))
    )
  )
)
